# EG4S20BG256_CoreBoard_A0_NATIVE.net
KiCad netlist of a schematic drawn in Altium Designer
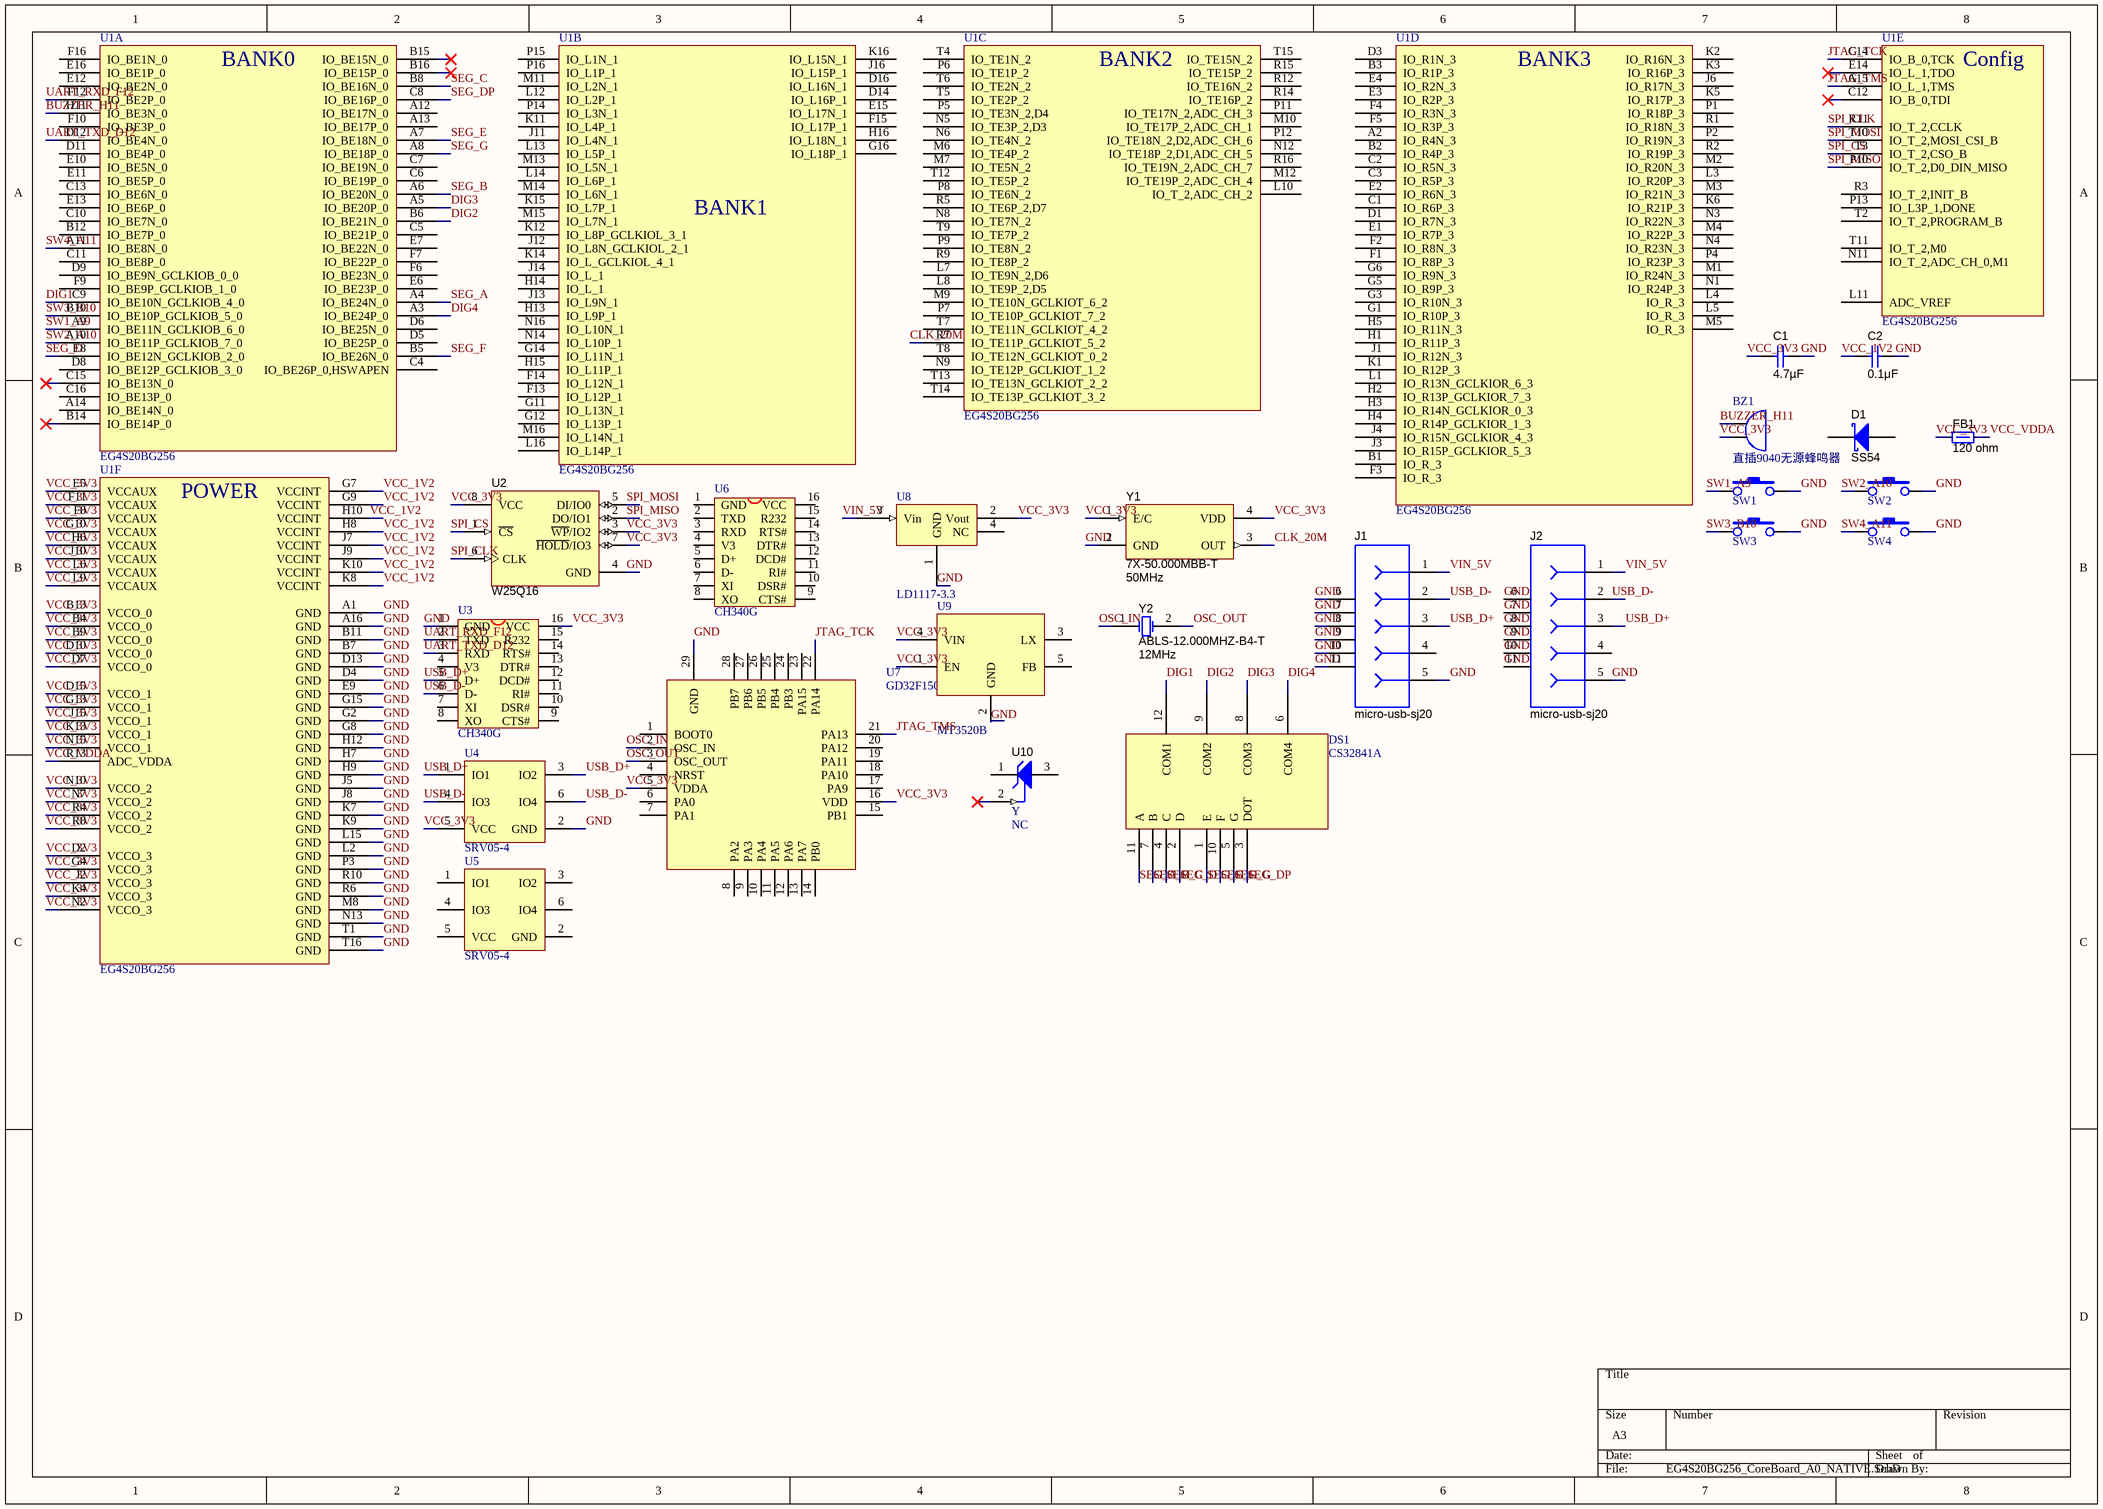
[diagram p0: EG4S20BG256_CoreBoard_A0_NATIVE.SchDoc]

(export (version "E")
  (design (tool "Eeschema 10.0.6"))
  (components
    (comp (ref "BZ1")
      (value "直插9040无源蜂鸣器")
      (footprint "BUZZER_9*9_4MM")
      (description "Buzzer, 74 dB min, 25V p-p, 8500pF @ 1kHz，直插9040无源蜂鸣器")
      (fields (field (name "MANUFACTURER") "Panasonic"))
      (libsource (lib "ANLOGIC开发板封装库") (part "BUZZER_EFBAA14D001"))
    )
    (comp (ref "C1")
      (value "GRM21BC81C475KA88L")
      (footprint "0805_HV")
      (description "CAP, CERM, 4.7 µF, 16 V, +/- 10%, X6S, 0805")
      (fields
        (field (name "VALUEDISPLAYED") "4.7µF")
        (field (name "MANUFACTURER") "MuRata")
        (field (name "PUBLISHER") "Texas Instruments")
      )
      (libsource (lib "ANLOGIC开发板封装库") (part "GRM21BC81C475KA88L"))
    )
    (comp (ref "C2")
      (value "C1005X7R1H104M")
      (footprint "0402")
      (description "CAP, CERM, 0.1 μF, 50 V, +/- 20%, X7R, 0402")
      (fields
        (field (name "VALUEDISPLAYED") "0.1μF")
        (field (name "MANUFACTURER") "TDK")
        (field (name "PUBLISHER") "Texas Instruments")
      )
      (libsource (lib "ANLOGIC开发板封装库") (part "C1005X7R1H104M_1"))
    )
    (comp (ref "D1")
      (value "SS54")
      (footprint "SMB")
      (description "Diode, Schottky, 40 V, 3A, SMB")
      (fields (field (name "MANUFACTURER") "Diodes Inc.") (field (name "PUBLISHER") "Texas Instruments"))
      (libsource (lib "ANLOGIC开发板封装库") (part "B340B-13-F"))
    )
    (comp (ref "DS1")
      (value "CS32841A")
      (footprint "CS2845AUR")
      (description "4位共阴数码管，红色")
      (libsource (lib "ANLOGIC开发板封装库") (part "4LED-ANODE"))
    )
    (comp (ref "FB1")
      (value "120 ohm")
      (footprint "0805_HV")
      (description "Ferrite Bead, 120 ohm @ 100 MHz, 0.2 A, 0805")
      (fields
        (field (name "PARTNUMBER") "GZ2012V121TF")
        (field (name "MANUFACTURER") "MuRata")
        (field (name "PUBLISHER") "Texas Instruments")
      )
      (libsource (lib "ANLOGIC开发板封装库") (part "BLM21BD121SN1D"))
    )
    (comp (ref "J1")
      (value "micro-usb-sj20")
      (footprint "YQMICRO-USB-SJ20")
      (description "Receptacle, Micro-USB-B, Right Angle, SMD")
      (fields
        (field (name "MANUFACTURER") "Molex")
        (field (name "SYMBOLCREATOR") "a0412235")
        (field (name "PUBLISHER") "Texas Instruments")
      )
      (libsource (lib "ANLOGIC开发板封装库") (part "105017-0001"))
    )
    (comp (ref "J2")
      (value "micro-usb-sj20")
      (footprint "YQMICRO-USB-SJ20")
      (description "Receptacle, Micro-USB-B, Right Angle, SMD")
      (fields
        (field (name "MANUFACTURER") "Molex")
        (field (name "SYMBOLCREATOR") "a0412235")
        (field (name "PUBLISHER") "Texas Instruments")
      )
      (libsource (lib "ANLOGIC开发板封装库") (part "105017-0001"))
    )
    (comp (ref "SW1")
      (value "贴片按键")
      (footprint "BUTTOM_T_6*6 *4.3")
      (description "米黄色圆形按键6*6*3.4")
      (libsource (lib "ANLOGIC开发板封装库") (part "SW-PB"))
    )
    (comp (ref "SW2")
      (value "贴片按键")
      (footprint "BUTTOM_T_6*6 *4.3")
      (description "米黄色圆形按键6*6*3.4")
      (libsource (lib "ANLOGIC开发板封装库") (part "SW-PB"))
    )
    (comp (ref "SW3")
      (value "贴片按键")
      (footprint "BUTTOM_T_6*6 *4.3")
      (description "米黄色圆形按键6*6*3.4")
      (libsource (lib "ANLOGIC开发板封装库") (part "SW-PB"))
    )
    (comp (ref "SW4")
      (value "贴片按键")
      (footprint "BUTTOM_T_6*6 *4.3")
      (description "米黄色圆形按键6*6*3.4")
      (libsource (lib "ANLOGIC开发板封装库") (part "SW-PB"))
    )
    (comp (ref "U1")
      (value "EG4S20BG256")
      (footprint "FBGA256")
      (libsource (lib "ANLOGIC开发板封装库") (part "EG4S20BG256"))
    )
    (comp (ref "U2")
      (value "W25Q16")
      (footprint "MICT-MW-8_N")
      (description "2.5V 8M-Bit Serial Flash Memory with Dual and Quad SPI, SOIC-8")
      (fields
        (field (name "PARTNUMBER") "W25Q16")
        (field (name "MANUFACTURER") "Winbond")
        (field (name "SYMBOLCREATOR") "Altium")
        (field (name "PUBLISHER") "Texas Instruments")
      )
      (libsource (lib "ANLOGIC开发板封装库") (part "W25Q80BLSNIG"))
    )
    (comp (ref "U3")
      (value "CH340G")
      (footprint "SOP16M")
      (description "USB2UART")
      (libsource (lib "ANLOGIC开发板封装库") (part "CH340G"))
    )
    (comp (ref "U4")
      (value "SRV05-4")
      (footprint "DBV0006A_N")
      (fields
        (field (name "MANUFACTURER") "Texas Instruments")
        (field (name "PARTNUMBER") "TPD4E001DBVR")
        (field (name "ALTERNATE PARTNUMBER") "Equivalent")
      )
      (libsource (lib "ANLOGIC开发板封装库") (part "TPD4E001DBVR"))
    )
    (comp (ref "U5")
      (value "SRV05-4")
      (footprint "DBV0006A_N")
      (fields
        (field (name "MANUFACTURER") "Texas Instruments")
        (field (name "PARTNUMBER") "TPD4E001DBVR")
        (field (name "ALTERNATE PARTNUMBER") "Equivalent")
      )
      (libsource (lib "ANLOGIC开发板封装库") (part "TPD4E001DBVR"))
    )
    (comp (ref "U6")
      (value "CH340G")
      (footprint "SOP16M")
      (description "USB2UART")
      (libsource (lib "ANLOGIC开发板封装库") (part "CH340G"))
    )
    (comp (ref "U7")
      (value "GD32F150G8U6")
      (footprint "WQFN-28_L4.0-W4.0-P0.40-BL-EP")
      (description "GD32F150U")
      (libsource (lib "ANLOGIC开发板封装库") (part "GD32F150U"))
    )
    (comp (ref "U8")
      (value "LD1117-3.3")
      (footprint "SOT223-L")
      (description "LDO电源")
      (libsource (lib "ANLOGIC开发板封装库") (part "AMS1117"))
    )
    (comp (ref "U9")
      (value "MT3520B")
      (footprint "DBV0005A_N")
      (description "1MHZ,2A,STEP-DOWM DC/DC")
      (libsource (lib "ANLOGIC开发板封装库") (part "RT8097"))
    )
    (comp (ref "U10")
      (value "Y")
      (footprint "DBZ0003A_N")
      (description "PRECISION PROGRAMMABLE REFERENCE, DBZ0003A")
      (fields
        (field (name "PARTNUMBER") "TL431AIDBZ")
        (field (name "MANUFACTURER") "Texas Instruments")
        (field (name "IGNORE") "Y")
        (field (name "PARAMETER 1") "NC")
        (field (name "SYMBOLCREATOR") "a0412235")
        (field (name "PUBLISHER") "Texas Instruments")
      )
      (libsource (lib "ANLOGIC开发板封装库") (part "TL431AIDBZ"))
    )
    (comp (ref "Y1")
      (value "7X-50.000MBB-T")
      (footprint "XTAL_NX3225SA")
      (description "Crystal, 有源晶振，Sealed Locked 50MHz, 15pF, SMD")
      (fields
        (field (name "MANUFACTURER") "TXC Corporation")
        (field (name "FREQUENCY") "50MHz")
        (field (name "SYMBOLCREATOR") "a0799628")
        (field (name "PUBLISHER") "Texas Instruments")
      )
      (libsource (lib "ANLOGIC开发板封装库") (part "7X-20.000MBB-T_1"))
    )
    (comp (ref "Y2")
      (value "ABLS-12.000MHZ-B4-T")
      (footprint "YQ_OSC5032")
      (description "Crystal, 12MHz, 18pF, SMD,无源")
      (fields
        (field (name "FREQUENCY") "12MHz")
        (field (name "MANUFACTURER") "Abracon Corportation")
        (field (name "SYMBOLCREATOR") "a0412235")
        (field (name "PUBLISHER") "Texas Instruments")
      )
      (libsource (lib "ANLOGIC开发板封装库") (part "ABLS-8.000MHZ-B4-T"))
    )
  )
  (nets
    (net (code "1") (name "/BUZZER_H11") (class "Default")
      (node (ref "BZ1") (pin "1") (pintype "passive"))
      (node (ref "U1") (pin "H11") (pinfunction "IO_BE3N_0_H11") (pintype "passive"))
    )
    (net (code "2") (name "/CLK_20M") (class "Default")
      (node (ref "U1") (pin "R7") (pinfunction "IO_TE11P_GCLKIOT_5_2_R7") (pintype "passive"))
      (node (ref "Y1") (pin "3") (pinfunction "OUT_3") (pintype "output"))
    )
    (net (code "3") (name "/DIG1") (class "Default")
      (node (ref "DS1") (pin "12") (pinfunction "COM1_12") (pintype "passive"))
      (node (ref "U1") (pin "C9") (pinfunction "IO_BE10N_GCLKIOB_4_0_C9") (pintype "passive"))
    )
    (net (code "4") (name "/DIG2") (class "Default")
      (node (ref "DS1") (pin "9") (pinfunction "COM2_9") (pintype "passive"))
      (node (ref "U1") (pin "B6") (pinfunction "IO_BE21N_0_B6") (pintype "passive"))
    )
    (net (code "5") (name "/DIG3") (class "Default")
      (node (ref "DS1") (pin "8") (pinfunction "COM3_8") (pintype "passive"))
      (node (ref "U1") (pin "A5") (pinfunction "IO_BE20P_0_A5") (pintype "passive"))
    )
    (net (code "6") (name "/DIG4") (class "Default")
      (node (ref "DS1") (pin "6") (pinfunction "COM4_6") (pintype "passive"))
      (node (ref "U1") (pin "A3") (pinfunction "IO_BE24P_0_A3") (pintype "passive"))
    )
    (net (code "7") (name "/GND") (class "Default")
      (node (ref "C1") (pin "1") (pinfunction "1_1") (pintype "passive"))
      (node (ref "C2") (pin "1") (pinfunction "1_1") (pintype "passive"))
      (node (ref "J1") (pin "10") (pintype "passive"))
      (node (ref "J1") (pin "11") (pintype "passive"))
      (node (ref "J1") (pin "5") (pintype "passive"))
      (node (ref "J1") (pin "6") (pintype "passive"))
      (node (ref "J1") (pin "7") (pintype "passive"))
      (node (ref "J1") (pin "8") (pintype "passive"))
      (node (ref "J1") (pin "9") (pintype "passive"))
      (node (ref "J2") (pin "10") (pintype "passive"))
      (node (ref "J2") (pin "11") (pintype "passive"))
      (node (ref "J2") (pin "5") (pintype "passive"))
      (node (ref "J2") (pin "6") (pintype "passive"))
      (node (ref "J2") (pin "7") (pintype "passive"))
      (node (ref "J2") (pin "8") (pintype "passive"))
      (node (ref "J2") (pin "9") (pintype "passive"))
      (node (ref "SW1") (pin "2") (pintype "passive"))
      (node (ref "SW2") (pin "2") (pintype "passive"))
      (node (ref "SW3") (pin "2") (pintype "passive"))
      (node (ref "SW4") (pin "2") (pintype "passive"))
      (node (ref "U1") (pin "A1") (pinfunction "GND_A1") (pintype "passive"))
      (node (ref "U1") (pin "A16") (pinfunction "GND_A16") (pintype "passive"))
      (node (ref "U1") (pin "B11") (pinfunction "GND_B11") (pintype "passive"))
      (node (ref "U1") (pin "B7") (pinfunction "GND_B7") (pintype "passive"))
      (node (ref "U1") (pin "D13") (pinfunction "GND_D13") (pintype "passive"))
      (node (ref "U1") (pin "D4") (pinfunction "GND_D4") (pintype "passive"))
      (node (ref "U1") (pin "E9") (pinfunction "GND_E9") (pintype "passive"))
      (node (ref "U1") (pin "G15") (pinfunction "GND_G15") (pintype "passive"))
      (node (ref "U1") (pin "G2") (pinfunction "GND_G2") (pintype "passive"))
      (node (ref "U1") (pin "G8") (pinfunction "GND_G8") (pintype "passive"))
      (node (ref "U1") (pin "H12") (pinfunction "GND_H12") (pintype "passive"))
      (node (ref "U1") (pin "H7") (pinfunction "GND_H7") (pintype "passive"))
      (node (ref "U1") (pin "H9") (pinfunction "GND_H9") (pintype "passive"))
      (node (ref "U1") (pin "J5") (pinfunction "GND_J5") (pintype "passive"))
      (node (ref "U1") (pin "J8") (pinfunction "GND_J8") (pintype "passive"))
      (node (ref "U1") (pin "K7") (pinfunction "GND_K7") (pintype "passive"))
      (node (ref "U1") (pin "K9") (pinfunction "GND_K9") (pintype "passive"))
      (node (ref "U1") (pin "L15") (pinfunction "GND_L15") (pintype "passive"))
      (node (ref "U1") (pin "L2") (pinfunction "GND_L2") (pintype "passive"))
      (node (ref "U1") (pin "M8") (pinfunction "GND_M8") (pintype "passive"))
      (node (ref "U1") (pin "N13") (pinfunction "GND_N13") (pintype "passive"))
      (node (ref "U1") (pin "P3") (pinfunction "GND_P3") (pintype "passive"))
      (node (ref "U1") (pin "R10") (pinfunction "GND_R10") (pintype "passive"))
      (node (ref "U1") (pin "R6") (pinfunction "GND_R6") (pintype "passive"))
      (node (ref "U1") (pin "T1") (pinfunction "GND_T1") (pintype "passive"))
      (node (ref "U1") (pin "T16") (pinfunction "GND_T16") (pintype "passive"))
      (node (ref "U2") (pin "4") (pinfunction "GND_4") (pintype "power_in"))
      (node (ref "U3") (pin "1") (pinfunction "GND_1") (pintype "passive"))
      (node (ref "U4") (pin "2") (pinfunction "GND_2") (pintype "power_in"))
      (node (ref "U7") (pin "29") (pinfunction "GND_29") (pintype "passive"))
      (node (ref "U8") (pin "1") (pinfunction "GND_1") (pintype "power_in"))
      (node (ref "U9") (pin "2") (pinfunction "GND_2") (pintype "passive"))
      (node (ref "Y1") (pin "2") (pinfunction "GND_2") (pintype "power_in"))
    )
    (net (code "8") (name "/JTAG_TCK") (class "Default")
      (node (ref "U1") (pin "C14") (pinfunction "IO_B_0,TCK_C14") (pintype "passive"))
      (node (ref "U7") (pin "22") (pinfunction "PA14_22") (pintype "passive"))
    )
    (net (code "9") (name "/JTAG_TMS") (class "Default")
      (node (ref "U1") (pin "A15") (pinfunction "IO_L_1,TMS_A15") (pintype "passive"))
      (node (ref "U7") (pin "21") (pinfunction "PA13_21") (pintype "passive"))
    )
    (net (code "10") (name "/OSC_IN") (class "Default")
      (node (ref "U7") (pin "2") (pinfunction "OSC_IN_2") (pintype "passive"))
      (node (ref "Y2") (pin "1") (pinfunction "OSC1_1") (pintype "passive"))
    )
    (net (code "11") (name "/OSC_OUT") (class "Default")
      (node (ref "U7") (pin "3") (pinfunction "OSC_OUT_3") (pintype "passive"))
      (node (ref "Y2") (pin "2") (pinfunction "OSC2_2") (pintype "passive"))
    )
    (net (code "12") (name "/SEG_A") (class "Default")
      (node (ref "DS1") (pin "11") (pinfunction "A_11") (pintype "passive"))
      (node (ref "U1") (pin "A4") (pinfunction "IO_BE24N_0_A4") (pintype "passive"))
    )
    (net (code "13") (name "/SEG_B") (class "Default")
      (node (ref "DS1") (pin "7") (pinfunction "B_7") (pintype "passive"))
      (node (ref "U1") (pin "A6") (pinfunction "IO_BE20N_0_A6") (pintype "passive"))
    )
    (net (code "14") (name "/SEG_C") (class "Default")
      (node (ref "DS1") (pin "4") (pinfunction "C_4") (pintype "passive"))
      (node (ref "U1") (pin "B8") (pinfunction "IO_BE16N_0_B8") (pintype "passive"))
    )
    (net (code "15") (name "/SEG_D") (class "Default")
      (node (ref "DS1") (pin "2") (pinfunction "D_2") (pintype "passive"))
      (node (ref "U1") (pin "E8") (pinfunction "IO_BE12N_GCLKIOB_2_0_E8") (pintype "passive"))
    )
    (net (code "16") (name "/SEG_DP") (class "Default")
      (node (ref "DS1") (pin "3") (pinfunction "DOT_3") (pintype "passive"))
      (node (ref "U1") (pin "C8") (pinfunction "IO_BE16P_0_C8") (pintype "passive"))
    )
    (net (code "17") (name "/SEG_E") (class "Default")
      (node (ref "DS1") (pin "1") (pinfunction "E_1") (pintype "passive"))
      (node (ref "U1") (pin "A7") (pinfunction "IO_BE18N_0_A7") (pintype "passive"))
    )
    (net (code "18") (name "/SEG_F") (class "Default")
      (node (ref "DS1") (pin "10") (pinfunction "F_10") (pintype "passive"))
      (node (ref "U1") (pin "B5") (pinfunction "IO_BE26N_0_B5") (pintype "passive"))
    )
    (net (code "19") (name "/SEG_G") (class "Default")
      (node (ref "DS1") (pin "5") (pinfunction "G_5") (pintype "passive"))
      (node (ref "U1") (pin "A8") (pinfunction "IO_BE18P_0_A8") (pintype "passive"))
    )
    (net (code "20") (name "/SPI_CLK") (class "Default")
      (node (ref "U1") (pin "R11") (pinfunction "IO_T_2,CCLK_R11") (pintype "passive"))
      (node (ref "U2") (pin "6") (pinfunction "CLK_6") (pintype "input"))
    )
    (net (code "21") (name "/SPI_CS") (class "Default")
      (node (ref "U1") (pin "T3") (pinfunction "IO_T_2,CSO_B_T3") (pintype "passive"))
      (node (ref "U2") (pin "1") (pinfunction "~{CS}_1") (pintype "input"))
    )
    (net (code "22") (name "/SPI_MISO") (class "Default")
      (node (ref "U1") (pin "P10") (pinfunction "IO_T_2,D0_DIN_MISO_P10") (pintype "passive"))
      (node (ref "U2") (pin "2") (pinfunction "DO/IO1_2") (pintype "bidirectional"))
    )
    (net (code "23") (name "/SPI_MOSI") (class "Default")
      (node (ref "U1") (pin "T10") (pinfunction "IO_T_2,MOSI_CSI_B_T10") (pintype "passive"))
      (node (ref "U2") (pin "5") (pinfunction "DI/IO0_5") (pintype "bidirectional"))
    )
    (net (code "24") (name "/SW1_A9") (class "Default")
      (node (ref "SW1") (pin "1") (pintype "passive"))
      (node (ref "U1") (pin "A9") (pinfunction "IO_BE11N_GCLKIOB_6_0_A9") (pintype "passive"))
    )
    (net (code "25") (name "/SW2_A10") (class "Default")
      (node (ref "SW2") (pin "1") (pintype "passive"))
      (node (ref "U1") (pin "A10") (pinfunction "IO_BE11P_GCLKIOB_7_0_A10") (pintype "passive"))
    )
    (net (code "26") (name "/SW3_B10") (class "Default")
      (node (ref "SW3") (pin "1") (pintype "passive"))
      (node (ref "U1") (pin "B10") (pinfunction "IO_BE10P_GCLKIOB_5_0_B10") (pintype "passive"))
    )
    (net (code "27") (name "/SW4_A11") (class "Default")
      (node (ref "SW4") (pin "1") (pintype "passive"))
      (node (ref "U1") (pin "A11") (pinfunction "IO_BE8N_0_A11") (pintype "passive"))
    )
    (net (code "28") (name "/UART_RXD_F12") (class "Default")
      (node (ref "U1") (pin "F12") (pinfunction "IO_BE2P_0_F12") (pintype "passive"))
      (node (ref "U3") (pin "2") (pinfunction "TXD_2") (pintype "passive"))
    )
    (net (code "29") (name "/UART_TXD_D12") (class "Default")
      (node (ref "U1") (pin "D12") (pinfunction "IO_BE4N_0_D12") (pintype "passive"))
      (node (ref "U3") (pin "3") (pinfunction "RXD_3") (pintype "passive"))
    )
    (net (code "30") (name "/USB_D+") (class "Default")
      (node (ref "J1") (pin "3") (pintype "passive"))
      (node (ref "J2") (pin "3") (pintype "passive"))
      (node (ref "U3") (pin "5") (pinfunction "D+_5") (pintype "passive"))
      (node (ref "U4") (pin "1") (pinfunction "IO1_1") (pintype "passive"))
      (node (ref "U4") (pin "3") (pinfunction "IO2_3") (pintype "passive"))
    )
    (net (code "31") (name "/USB_D-") (class "Default")
      (node (ref "J1") (pin "2") (pintype "passive"))
      (node (ref "J2") (pin "2") (pintype "passive"))
      (node (ref "U3") (pin "6") (pinfunction "D-_6") (pintype "passive"))
      (node (ref "U4") (pin "4") (pinfunction "IO3_4") (pintype "passive"))
      (node (ref "U4") (pin "6") (pinfunction "IO4_6") (pintype "passive"))
    )
    (net (code "32") (name "/VCC_1V2") (class "Default")
      (node (ref "C2") (pin "2") (pinfunction "2_2") (pintype "passive"))
      (node (ref "U1") (pin "G7") (pinfunction "VCCINT_G7") (pintype "passive"))
      (node (ref "U1") (pin "G9") (pinfunction "VCCINT_G9") (pintype "passive"))
      (node (ref "U1") (pin "H10") (pinfunction "VCCINT_H10") (pintype "passive"))
      (node (ref "U1") (pin "H8") (pinfunction "VCCINT_H8") (pintype "passive"))
      (node (ref "U1") (pin "J7") (pinfunction "VCCINT_J7") (pintype "passive"))
      (node (ref "U1") (pin "J9") (pinfunction "VCCINT_J9") (pintype "passive"))
      (node (ref "U1") (pin "K10") (pinfunction "VCCINT_K10") (pintype "passive"))
      (node (ref "U1") (pin "K8") (pinfunction "VCCINT_K8") (pintype "passive"))
    )
    (net (code "33") (name "/VCC_3V3") (class "Default")
      (node (ref "BZ1") (pin "2") (pintype "passive"))
      (node (ref "C1") (pin "2") (pinfunction "2_2") (pintype "passive"))
      (node (ref "FB1") (pin "1") (pinfunction "1_1") (pintype "passive"))
      (node (ref "U1") (pin "B13") (pinfunction "VCCO_0_B13") (pintype "passive"))
      (node (ref "U1") (pin "B4") (pinfunction "VCCO_0_B4") (pintype "passive"))
      (node (ref "U1") (pin "B9") (pinfunction "VCCO_0_B9") (pintype "passive"))
      (node (ref "U1") (pin "D10") (pinfunction "VCCO_0_D10") (pintype "passive"))
      (node (ref "U1") (pin "D15") (pinfunction "VCCO_1_D15") (pintype "passive"))
      (node (ref "U1") (pin "D2") (pinfunction "VCCO_3_D2") (pintype "passive"))
      (node (ref "U1") (pin "D7") (pinfunction "VCCO_0_D7") (pintype "passive"))
      (node (ref "U1") (pin "E5") (pinfunction "VCCAUX_E5") (pintype "passive"))
      (node (ref "U1") (pin "F11") (pinfunction "VCCAUX_F11") (pintype "passive"))
      (node (ref "U1") (pin "F8") (pinfunction "VCCAUX_F8") (pintype "passive"))
      (node (ref "U1") (pin "G10") (pinfunction "VCCAUX_G10") (pintype "passive"))
      (node (ref "U1") (pin "G13") (pinfunction "VCCO_1_G13") (pintype "passive"))
      (node (ref "U1") (pin "G4") (pinfunction "VCCO_3_G4") (pintype "passive"))
      (node (ref "U1") (pin "H6") (pinfunction "VCCAUX_H6") (pintype "passive"))
      (node (ref "U1") (pin "J10") (pinfunction "VCCAUX_J10") (pintype "passive"))
      (node (ref "U1") (pin "J15") (pinfunction "VCCO_1_J15") (pintype "passive"))
      (node (ref "U1") (pin "J2") (pinfunction "VCCO_3_J2") (pintype "passive"))
      (node (ref "U1") (pin "K13") (pinfunction "VCCO_1_K13") (pintype "passive"))
      (node (ref "U1") (pin "K4") (pinfunction "VCCO_3_K4") (pintype "passive"))
      (node (ref "U1") (pin "L6") (pinfunction "VCCAUX_L6") (pintype "passive"))
      (node (ref "U1") (pin "L9") (pinfunction "VCCAUX_L9") (pintype "passive"))
      (node (ref "U1") (pin "N10") (pinfunction "VCCO_2_N10") (pintype "passive"))
      (node (ref "U1") (pin "N15") (pinfunction "VCCO_1_N15") (pintype "passive"))
      (node (ref "U1") (pin "N2") (pinfunction "VCCO_3_N2") (pintype "passive"))
      (node (ref "U1") (pin "N7") (pinfunction "VCCO_2_N7") (pintype "passive"))
      (node (ref "U1") (pin "R4") (pinfunction "VCCO_2_R4") (pintype "passive"))
      (node (ref "U1") (pin "R8") (pinfunction "VCCO_2_R8") (pintype "passive"))
      (node (ref "U2") (pin "3") (pinfunction "~{WP}/IO2_3") (pintype "bidirectional"))
      (node (ref "U2") (pin "7") (pinfunction "~{HOLD}/IO3_7") (pintype "bidirectional"))
      (node (ref "U2") (pin "8") (pinfunction "VCC_8") (pintype "power_in"))
      (node (ref "U3") (pin "16") (pinfunction "VCC_16") (pintype "passive"))
      (node (ref "U4") (pin "5") (pinfunction "VCC_5") (pintype "power_in"))
      (node (ref "U7") (pin "16") (pinfunction "VDD_16") (pintype "passive"))
      (node (ref "U7") (pin "5") (pinfunction "VDDA_5") (pintype "passive"))
      (node (ref "U8") (pin "2") (pinfunction "Vout_2") (pintype "power_in"))
      (node (ref "U9") (pin "1") (pinfunction "EN_1") (pintype "passive"))
      (node (ref "U9") (pin "4") (pinfunction "VIN_4") (pintype "passive"))
      (node (ref "Y1") (pin "1") (pinfunction "E/C_1") (pintype "input"))
      (node (ref "Y1") (pin "4") (pinfunction "VDD_4") (pintype "power_in"))
    )
    (net (code "34") (name "/VCC_VDDA") (class "Default")
      (node (ref "FB1") (pin "2") (pinfunction "2_2") (pintype "passive"))
      (node (ref "U1") (pin "R13") (pinfunction "ADC_VDDA_R13") (pintype "passive"))
    )
    (net (code "35") (name "/VIN_5V") (class "Default")
      (node (ref "J1") (pin "1") (pintype "passive"))
      (node (ref "J2") (pin "1") (pintype "passive"))
      (node (ref "U8") (pin "3") (pinfunction "Vin_3") (pintype "input"))
    )
    (net (code "36") (name "unconnected-(D1-A-Pad2)") (class "Default")
      (node (ref "D1") (pin "2") (pinfunction "A_2") (pintype "passive"))
    )
    (net (code "37") (name "unconnected-(D1-K-Pad1)") (class "Default")
      (node (ref "D1") (pin "1") (pinfunction "K_1") (pintype "passive"))
    )
    (net (code "38") (name "unconnected-(J1-Pad4)") (class "Default")
      (node (ref "J1") (pin "4") (pintype "passive"))
    )
    (net (code "39") (name "unconnected-(J2-Pad4)") (class "Default")
      (node (ref "J2") (pin "4") (pintype "passive"))
    )
    (net (code "40") (name "unconnected-(U1A-IO_BE1N_0-PadF16)") (class "Default")
      (node (ref "U1") (pin "F16") (pinfunction "IO_BE1N_0_F16") (pintype "passive"))
    )
    (net (code "41") (name "unconnected-(U1A-IO_BE1P_0-PadE16)") (class "Default")
      (node (ref "U1") (pin "E16") (pinfunction "IO_BE1P_0_E16") (pintype "passive"))
    )
    (net (code "42") (name "unconnected-(U1A-IO_BE2N_0-PadE12)") (class "Default")
      (node (ref "U1") (pin "E12") (pinfunction "IO_BE2N_0_E12") (pintype "passive"))
    )
    (net (code "43") (name "unconnected-(U1A-IO_BE3P_0-PadF10)") (class "Default")
      (node (ref "U1") (pin "F10") (pinfunction "IO_BE3P_0_F10") (pintype "passive"))
    )
    (net (code "44") (name "unconnected-(U1A-IO_BE4P_0-PadD11)") (class "Default")
      (node (ref "U1") (pin "D11") (pinfunction "IO_BE4P_0_D11") (pintype "passive"))
    )
    (net (code "45") (name "unconnected-(U1A-IO_BE5N_0-PadE10)") (class "Default")
      (node (ref "U1") (pin "E10") (pinfunction "IO_BE5N_0_E10") (pintype "passive"))
    )
    (net (code "46") (name "unconnected-(U1A-IO_BE5P_0-PadE11)") (class "Default")
      (node (ref "U1") (pin "E11") (pinfunction "IO_BE5P_0_E11") (pintype "passive"))
    )
    (net (code "47") (name "unconnected-(U1A-IO_BE6N_0-PadC13)") (class "Default")
      (node (ref "U1") (pin "C13") (pinfunction "IO_BE6N_0_C13") (pintype "passive"))
    )
    (net (code "48") (name "unconnected-(U1A-IO_BE6P_0-PadE13)") (class "Default")
      (node (ref "U1") (pin "E13") (pinfunction "IO_BE6P_0_E13") (pintype "passive"))
    )
    (net (code "49") (name "unconnected-(U1A-IO_BE7N_0-PadC10)") (class "Default")
      (node (ref "U1") (pin "C10") (pinfunction "IO_BE7N_0_C10") (pintype "passive"))
    )
    (net (code "50") (name "unconnected-(U1A-IO_BE7P_0-PadB12)") (class "Default")
      (node (ref "U1") (pin "B12") (pinfunction "IO_BE7P_0_B12") (pintype "passive"))
    )
    (net (code "51") (name "unconnected-(U1A-IO_BE8P_0-PadC11)") (class "Default")
      (node (ref "U1") (pin "C11") (pinfunction "IO_BE8P_0_C11") (pintype "passive"))
    )
    (net (code "52") (name "unconnected-(U1A-IO_BE9N_GCLKIOB_0_0-PadD9)") (class "Default")
      (node (ref "U1") (pin "D9") (pinfunction "IO_BE9N_GCLKIOB_0_0_D9") (pintype "passive"))
    )
    (net (code "53") (name "unconnected-(U1A-IO_BE9P_GCLKIOB_1_0-PadF9)") (class "Default")
      (node (ref "U1") (pin "F9") (pinfunction "IO_BE9P_GCLKIOB_1_0_F9") (pintype "passive"))
    )
    (net (code "54") (name "unconnected-(U1A-IO_BE12P_GCLKIOB_3_0-PadD8)") (class "Default")
      (node (ref "U1") (pin "D8") (pinfunction "IO_BE12P_GCLKIOB_3_0_D8") (pintype "passive"))
    )
    (net (code "55") (name "unconnected-(U1A-IO_BE13N_0-PadC15)") (class "Default")
      (node (ref "U1") (pin "C15") (pinfunction "IO_BE13N_0_C15") (pintype "passive+no_connect"))
    )
    (net (code "56") (name "unconnected-(U1A-IO_BE13P_0-PadC16)") (class "Default")
      (node (ref "U1") (pin "C16") (pinfunction "IO_BE13P_0_C16") (pintype "passive"))
    )
    (net (code "57") (name "unconnected-(U1A-IO_BE14N_0-PadA14)") (class "Default")
      (node (ref "U1") (pin "A14") (pinfunction "IO_BE14N_0_A14") (pintype "passive"))
    )
    (net (code "58") (name "unconnected-(U1A-IO_BE14P_0-PadB14)") (class "Default")
      (node (ref "U1") (pin "B14") (pinfunction "IO_BE14P_0_B14") (pintype "passive+no_connect"))
    )
    (net (code "59") (name "unconnected-(U1A-IO_BE15N_0-PadB15)") (class "Default")
      (node (ref "U1") (pin "B15") (pinfunction "IO_BE15N_0_B15") (pintype "passive+no_connect"))
    )
    (net (code "60") (name "unconnected-(U1A-IO_BE15P_0-PadB16)") (class "Default")
      (node (ref "U1") (pin "B16") (pinfunction "IO_BE15P_0_B16") (pintype "passive+no_connect"))
    )
    (net (code "61") (name "unconnected-(U1A-IO_BE17N_0-PadA12)") (class "Default")
      (node (ref "U1") (pin "A12") (pinfunction "IO_BE17N_0_A12") (pintype "passive"))
    )
    (net (code "62") (name "unconnected-(U1A-IO_BE17P_0-PadA13)") (class "Default")
      (node (ref "U1") (pin "A13") (pinfunction "IO_BE17P_0_A13") (pintype "passive"))
    )
    (net (code "63") (name "unconnected-(U1A-IO_BE19N_0-PadC7)") (class "Default")
      (node (ref "U1") (pin "C7") (pinfunction "IO_BE19N_0_C7") (pintype "passive"))
    )
    (net (code "64") (name "unconnected-(U1A-IO_BE19P_0-PadC6)") (class "Default")
      (node (ref "U1") (pin "C6") (pinfunction "IO_BE19P_0_C6") (pintype "passive"))
    )
    (net (code "65") (name "unconnected-(U1A-IO_BE21P_0-PadC5)") (class "Default")
      (node (ref "U1") (pin "C5") (pinfunction "IO_BE21P_0_C5") (pintype "passive"))
    )
    (net (code "66") (name "unconnected-(U1A-IO_BE22N_0-PadE7)") (class "Default")
      (node (ref "U1") (pin "E7") (pinfunction "IO_BE22N_0_E7") (pintype "passive"))
    )
    (net (code "67") (name "unconnected-(U1A-IO_BE22P_0-PadF7)") (class "Default")
      (node (ref "U1") (pin "F7") (pinfunction "IO_BE22P_0_F7") (pintype "passive"))
    )
    (net (code "68") (name "unconnected-(U1A-IO_BE23N_0-PadF6)") (class "Default")
      (node (ref "U1") (pin "F6") (pinfunction "IO_BE23N_0_F6") (pintype "passive"))
    )
    (net (code "69") (name "unconnected-(U1A-IO_BE23P_0-PadE6)") (class "Default")
      (node (ref "U1") (pin "E6") (pinfunction "IO_BE23P_0_E6") (pintype "passive"))
    )
    (net (code "70") (name "unconnected-(U1A-IO_BE25N_0-PadD6)") (class "Default")
      (node (ref "U1") (pin "D6") (pinfunction "IO_BE25N_0_D6") (pintype "passive"))
    )
    (net (code "71") (name "unconnected-(U1A-IO_BE25P_0-PadD5)") (class "Default")
      (node (ref "U1") (pin "D5") (pinfunction "IO_BE25P_0_D5") (pintype "passive"))
    )
    (net (code "72") (name "unconnected-(U1A-IO_BE26P_0,HSWAPEN-PadC4)") (class "Default")
      (node (ref "U1") (pin "C4") (pinfunction "IO_BE26P_0,HSWAPEN_C4") (pintype "passive"))
    )
    (net (code "73") (name "unconnected-(U1B-IO_L1N_1-PadP15)") (class "Default")
      (node (ref "U1") (pin "P15") (pinfunction "IO_L1N_1_P15") (pintype "passive"))
    )
    (net (code "74") (name "unconnected-(U1B-IO_L1P_1-PadP16)") (class "Default")
      (node (ref "U1") (pin "P16") (pinfunction "IO_L1P_1_P16") (pintype "passive"))
    )
    (net (code "75") (name "unconnected-(U1B-IO_L2N_1-PadM11)") (class "Default")
      (node (ref "U1") (pin "M11") (pinfunction "IO_L2N_1_M11") (pintype "passive"))
    )
    (net (code "76") (name "unconnected-(U1B-IO_L2P_1-PadL12)") (class "Default")
      (node (ref "U1") (pin "L12") (pinfunction "IO_L2P_1_L12") (pintype "passive"))
    )
    (net (code "77") (name "unconnected-(U1B-IO_L3N_1-PadP14)") (class "Default")
      (node (ref "U1") (pin "P14") (pinfunction "IO_L3N_1_P14") (pintype "passive"))
    )
    (net (code "78") (name "unconnected-(U1B-IO_L4N_1-PadJ11)") (class "Default")
      (node (ref "U1") (pin "J11") (pinfunction "IO_L4N_1_J11") (pintype "passive"))
    )
    (net (code "79") (name "unconnected-(U1B-IO_L4P_1-PadK11)") (class "Default")
      (node (ref "U1") (pin "K11") (pinfunction "IO_L4P_1_K11") (pintype "passive"))
    )
    (net (code "80") (name "unconnected-(U1B-IO_L5N_1-PadM13)") (class "Default")
      (node (ref "U1") (pin "M13") (pinfunction "IO_L5N_1_M13") (pintype "passive"))
    )
    (net (code "81") (name "unconnected-(U1B-IO_L5P_1-PadL13)") (class "Default")
      (node (ref "U1") (pin "L13") (pinfunction "IO_L5P_1_L13") (pintype "passive"))
    )
    (net (code "82") (name "unconnected-(U1B-IO_L6N_1-PadM14)") (class "Default")
      (node (ref "U1") (pin "M14") (pinfunction "IO_L6N_1_M14") (pintype "passive"))
    )
    (net (code "83") (name "unconnected-(U1B-IO_L6P_1-PadL14)") (class "Default")
      (node (ref "U1") (pin "L14") (pinfunction "IO_L6P_1_L14") (pintype "passive"))
    )
    (net (code "84") (name "unconnected-(U1B-IO_L7N_1-PadM15)") (class "Default")
      (node (ref "U1") (pin "M15") (pinfunction "IO_L7N_1_M15") (pintype "passive"))
    )
    (net (code "85") (name "unconnected-(U1B-IO_L7P_1-PadK15)") (class "Default")
      (node (ref "U1") (pin "K15") (pinfunction "IO_L7P_1_K15") (pintype "passive"))
    )
    (net (code "86") (name "unconnected-(U1B-IO_L8N_GCLKIOL_2_1-PadJ12)") (class "Default")
      (node (ref "U1") (pin "J12") (pinfunction "IO_L8N_GCLKIOL_2_1_J12") (pintype "passive"))
    )
    (net (code "87") (name "unconnected-(U1B-IO_L8P_GCLKIOL_3_1-PadK12)") (class "Default")
      (node (ref "U1") (pin "K12") (pinfunction "IO_L8P_GCLKIOL_3_1_K12") (pintype "passive"))
    )
    (net (code "88") (name "unconnected-(U1B-IO_L9N_1-PadJ13)") (class "Default")
      (node (ref "U1") (pin "J13") (pinfunction "IO_L9N_1_J13") (pintype "passive"))
    )
    (net (code "89") (name "unconnected-(U1B-IO_L9P_1-PadH13)") (class "Default")
      (node (ref "U1") (pin "H13") (pinfunction "IO_L9P_1_H13") (pintype "passive"))
    )
    (net (code "90") (name "unconnected-(U1B-IO_L10N_1-PadN16)") (class "Default")
      (node (ref "U1") (pin "N16") (pinfunction "IO_L10N_1_N16") (pintype "passive"))
    )
    (net (code "91") (name "unconnected-(U1B-IO_L10P_1-PadN14)") (class "Default")
      (node (ref "U1") (pin "N14") (pinfunction "IO_L10P_1_N14") (pintype "passive"))
    )
    (net (code "92") (name "unconnected-(U1B-IO_L11N_1-PadG14)") (class "Default")
      (node (ref "U1") (pin "G14") (pinfunction "IO_L11N_1_G14") (pintype "passive"))
    )
    (net (code "93") (name "unconnected-(U1B-IO_L11P_1-PadH15)") (class "Default")
      (node (ref "U1") (pin "H15") (pinfunction "IO_L11P_1_H15") (pintype "passive"))
    )
    (net (code "94") (name "unconnected-(U1B-IO_L12N_1-PadF14)") (class "Default")
      (node (ref "U1") (pin "F14") (pinfunction "IO_L12N_1_F14") (pintype "passive"))
    )
    (net (code "95") (name "unconnected-(U1B-IO_L12P_1-PadF13)") (class "Default")
      (node (ref "U1") (pin "F13") (pinfunction "IO_L12P_1_F13") (pintype "passive"))
    )
    (net (code "96") (name "unconnected-(U1B-IO_L13N_1-PadG11)") (class "Default")
      (node (ref "U1") (pin "G11") (pinfunction "IO_L13N_1_G11") (pintype "passive"))
    )
    (net (code "97") (name "unconnected-(U1B-IO_L13P_1-PadG12)") (class "Default")
      (node (ref "U1") (pin "G12") (pinfunction "IO_L13P_1_G12") (pintype "passive"))
    )
    (net (code "98") (name "unconnected-(U1B-IO_L14N_1-PadM16)") (class "Default")
      (node (ref "U1") (pin "M16") (pinfunction "IO_L14N_1_M16") (pintype "passive"))
    )
    (net (code "99") (name "unconnected-(U1B-IO_L14P_1-PadL16)") (class "Default")
      (node (ref "U1") (pin "L16") (pinfunction "IO_L14P_1_L16") (pintype "passive"))
    )
    (net (code "100") (name "unconnected-(U1B-IO_L15N_1-PadK16)") (class "Default")
      (node (ref "U1") (pin "K16") (pinfunction "IO_L15N_1_K16") (pintype "passive"))
    )
    (net (code "101") (name "unconnected-(U1B-IO_L15P_1-PadJ16)") (class "Default")
      (node (ref "U1") (pin "J16") (pinfunction "IO_L15P_1_J16") (pintype "passive"))
    )
    (net (code "102") (name "unconnected-(U1B-IO_L16N_1-PadD16)") (class "Default")
      (node (ref "U1") (pin "D16") (pinfunction "IO_L16N_1_D16") (pintype "passive"))
    )
    (net (code "103") (name "unconnected-(U1B-IO_L16P_1-PadD14)") (class "Default")
      (node (ref "U1") (pin "D14") (pinfunction "IO_L16P_1_D14") (pintype "passive"))
    )
    (net (code "104") (name "unconnected-(U1B-IO_L17N_1-PadE15)") (class "Default")
      (node (ref "U1") (pin "E15") (pinfunction "IO_L17N_1_E15") (pintype "passive"))
    )
    (net (code "105") (name "unconnected-(U1B-IO_L17P_1-PadF15)") (class "Default")
      (node (ref "U1") (pin "F15") (pinfunction "IO_L17P_1_F15") (pintype "passive"))
    )
    (net (code "106") (name "unconnected-(U1B-IO_L18N_1-PadH16)") (class "Default")
      (node (ref "U1") (pin "H16") (pinfunction "IO_L18N_1_H16") (pintype "passive"))
    )
    (net (code "107") (name "unconnected-(U1B-IO_L18P_1-PadG16)") (class "Default")
      (node (ref "U1") (pin "G16") (pinfunction "IO_L18P_1_G16") (pintype "passive"))
    )
    (net (code "108") (name "unconnected-(U1B-IO_L_1-PadH14)") (class "Default")
      (node (ref "U1") (pin "H14") (pinfunction "IO_L_1_H14") (pintype "passive"))
    )
    (net (code "109") (name "unconnected-(U1B-IO_L_1-PadJ14)") (class "Default")
      (node (ref "U1") (pin "J14") (pinfunction "IO_L_1_J14") (pintype "passive"))
    )
    (net (code "110") (name "unconnected-(U1B-IO_L_GCLKIOL_4_1-PadK14)") (class "Default")
      (node (ref "U1") (pin "K14") (pinfunction "IO_L_GCLKIOL_4_1_K14") (pintype "passive"))
    )
    (net (code "111") (name "unconnected-(U1C-IO_TE1N_2-PadT4)") (class "Default")
      (node (ref "U1") (pin "T4") (pinfunction "IO_TE1N_2_T4") (pintype "passive"))
    )
    (net (code "112") (name "unconnected-(U1C-IO_TE1P_2-PadP6)") (class "Default")
      (node (ref "U1") (pin "P6") (pinfunction "IO_TE1P_2_P6") (pintype "passive"))
    )
    (net (code "113") (name "unconnected-(U1C-IO_TE2N_2-PadT6)") (class "Default")
      (node (ref "U1") (pin "T6") (pinfunction "IO_TE2N_2_T6") (pintype "passive"))
    )
    (net (code "114") (name "unconnected-(U1C-IO_TE2P_2-PadT5)") (class "Default")
      (node (ref "U1") (pin "T5") (pinfunction "IO_TE2P_2_T5") (pintype "passive"))
    )
    (net (code "115") (name "unconnected-(U1C-IO_TE3N_2,D4-PadP5)") (class "Default")
      (node (ref "U1") (pin "P5") (pinfunction "IO_TE3N_2,D4_P5") (pintype "passive"))
    )
    (net (code "116") (name "unconnected-(U1C-IO_TE3P_2,D3-PadN5)") (class "Default")
      (node (ref "U1") (pin "N5") (pinfunction "IO_TE3P_2,D3_N5") (pintype "passive"))
    )
    (net (code "117") (name "unconnected-(U1C-IO_TE4N_2-PadN6)") (class "Default")
      (node (ref "U1") (pin "N6") (pinfunction "IO_TE4N_2_N6") (pintype "passive"))
    )
    (net (code "118") (name "unconnected-(U1C-IO_TE4P_2-PadM6)") (class "Default")
      (node (ref "U1") (pin "M6") (pinfunction "IO_TE4P_2_M6") (pintype "passive"))
    )
    (net (code "119") (name "unconnected-(U1C-IO_TE5N_2-PadM7)") (class "Default")
      (node (ref "U1") (pin "M7") (pinfunction "IO_TE5N_2_M7") (pintype "passive"))
    )
    (net (code "120") (name "unconnected-(U1C-IO_TE5P_2-PadT12)") (class "Default")
      (node (ref "U1") (pin "T12") (pinfunction "IO_TE5P_2_T12") (pintype "passive"))
    )
    (net (code "121") (name "unconnected-(U1C-IO_TE6N_2-PadP8)") (class "Default")
      (node (ref "U1") (pin "P8") (pinfunction "IO_TE6N_2_P8") (pintype "passive"))
    )
    (net (code "122") (name "unconnected-(U1C-IO_TE6P_2,D7-PadR5)") (class "Default")
      (node (ref "U1") (pin "R5") (pinfunction "IO_TE6P_2,D7_R5") (pintype "passive"))
    )
    (net (code "123") (name "unconnected-(U1C-IO_TE7N_2-PadN8)") (class "Default")
      (node (ref "U1") (pin "N8") (pinfunction "IO_TE7N_2_N8") (pintype "passive"))
    )
    (net (code "124") (name "unconnected-(U1C-IO_TE7P_2-PadT9)") (class "Default")
      (node (ref "U1") (pin "T9") (pinfunction "IO_TE7P_2_T9") (pintype "passive"))
    )
    (net (code "125") (name "unconnected-(U1C-IO_TE8N_2-PadP9)") (class "Default")
      (node (ref "U1") (pin "P9") (pinfunction "IO_TE8N_2_P9") (pintype "passive"))
    )
    (net (code "126") (name "unconnected-(U1C-IO_TE8P_2-PadR9)") (class "Default")
      (node (ref "U1") (pin "R9") (pinfunction "IO_TE8P_2_R9") (pintype "passive"))
    )
    (net (code "127") (name "unconnected-(U1C-IO_TE9N_2,D6-PadL7)") (class "Default")
      (node (ref "U1") (pin "L7") (pinfunction "IO_TE9N_2,D6_L7") (pintype "passive"))
    )
    (net (code "128") (name "unconnected-(U1C-IO_TE9P_2,D5-PadL8)") (class "Default")
      (node (ref "U1") (pin "L8") (pinfunction "IO_TE9P_2,D5_L8") (pintype "passive"))
    )
    (net (code "129") (name "unconnected-(U1C-IO_TE10N_GCLKIOT_6_2-PadM9)") (class "Default")
      (node (ref "U1") (pin "M9") (pinfunction "IO_TE10N_GCLKIOT_6_2_M9") (pintype "passive"))
    )
    (net (code "130") (name "unconnected-(U1C-IO_TE10P_GCLKIOT_7_2-PadP7)") (class "Default")
      (node (ref "U1") (pin "P7") (pinfunction "IO_TE10P_GCLKIOT_7_2_P7") (pintype "passive"))
    )
    (net (code "131") (name "unconnected-(U1C-IO_TE11N_GCLKIOT_4_2-PadT7)") (class "Default")
      (node (ref "U1") (pin "T7") (pinfunction "IO_TE11N_GCLKIOT_4_2_T7") (pintype "passive"))
    )
    (net (code "132") (name "unconnected-(U1C-IO_TE12N_GCLKIOT_0_2-PadT8)") (class "Default")
      (node (ref "U1") (pin "T8") (pinfunction "IO_TE12N_GCLKIOT_0_2_T8") (pintype "passive"))
    )
    (net (code "133") (name "unconnected-(U1C-IO_TE12P_GCLKIOT_1_2-PadN9)") (class "Default")
      (node (ref "U1") (pin "N9") (pinfunction "IO_TE12P_GCLKIOT_1_2_N9") (pintype "passive"))
    )
    (net (code "134") (name "unconnected-(U1C-IO_TE13N_GCLKIOT_2_2-PadT13)") (class "Default")
      (node (ref "U1") (pin "T13") (pinfunction "IO_TE13N_GCLKIOT_2_2_T13") (pintype "passive"))
    )
    (net (code "135") (name "unconnected-(U1C-IO_TE13P_GCLKIOT_3_2-PadT14)") (class "Default")
      (node (ref "U1") (pin "T14") (pinfunction "IO_TE13P_GCLKIOT_3_2_T14") (pintype "passive"))
    )
    (net (code "136") (name "unconnected-(U1C-IO_TE15N_2-PadT15)") (class "Default")
      (node (ref "U1") (pin "T15") (pinfunction "IO_TE15N_2_T15") (pintype "passive"))
    )
    (net (code "137") (name "unconnected-(U1C-IO_TE15P_2-PadR15)") (class "Default")
      (node (ref "U1") (pin "R15") (pinfunction "IO_TE15P_2_R15") (pintype "passive"))
    )
    (net (code "138") (name "unconnected-(U1C-IO_TE16N_2-PadR12)") (class "Default")
      (node (ref "U1") (pin "R12") (pinfunction "IO_TE16N_2_R12") (pintype "passive"))
    )
    (net (code "139") (name "unconnected-(U1C-IO_TE16P_2-PadR14)") (class "Default")
      (node (ref "U1") (pin "R14") (pinfunction "IO_TE16P_2_R14") (pintype "passive"))
    )
    (net (code "140") (name "unconnected-(U1C-IO_TE17N_2,ADC_CH_3-PadP11)") (class "Default")
      (node (ref "U1") (pin "P11") (pinfunction "IO_TE17N_2,ADC_CH_3_P11") (pintype "passive"))
    )
    (net (code "141") (name "unconnected-(U1C-IO_TE17P_2,ADC_CH_1-PadM10)") (class "Default")
      (node (ref "U1") (pin "M10") (pinfunction "IO_TE17P_2,ADC_CH_1_M10") (pintype "passive"))
    )
    (net (code "142") (name "unconnected-(U1C-IO_TE18N_2,D2,ADC_CH_6-PadP12)") (class "Default")
      (node (ref "U1") (pin "P12") (pinfunction "IO_TE18N_2,D2,ADC_CH_6_P12") (pintype "passive"))
    )
    (net (code "143") (name "unconnected-(U1C-IO_TE18P_2,D1,ADC_CH_5-PadN12)") (class "Default")
      (node (ref "U1") (pin "N12") (pinfunction "IO_TE18P_2,D1,ADC_CH_5_N12") (pintype "passive"))
    )
    (net (code "144") (name "unconnected-(U1C-IO_TE19N_2,ADC_CH_7-PadR16)") (class "Default")
      (node (ref "U1") (pin "R16") (pinfunction "IO_TE19N_2,ADC_CH_7_R16") (pintype "passive"))
    )
    (net (code "145") (name "unconnected-(U1C-IO_TE19P_2,ADC_CH_4-PadM12)") (class "Default")
      (node (ref "U1") (pin "M12") (pinfunction "IO_TE19P_2,ADC_CH_4_M12") (pintype "passive"))
    )
    (net (code "146") (name "unconnected-(U1C-IO_T_2,ADC_CH_2-PadL10)") (class "Default")
      (node (ref "U1") (pin "L10") (pinfunction "IO_T_2,ADC_CH_2_L10") (pintype "passive"))
    )
    (net (code "147") (name "unconnected-(U1D-IO_R1N_3-PadD3)") (class "Default")
      (node (ref "U1") (pin "D3") (pinfunction "IO_R1N_3_D3") (pintype "passive"))
    )
    (net (code "148") (name "unconnected-(U1D-IO_R1P_3-PadB3)") (class "Default")
      (node (ref "U1") (pin "B3") (pinfunction "IO_R1P_3_B3") (pintype "passive"))
    )
    (net (code "149") (name "unconnected-(U1D-IO_R2N_3-PadE4)") (class "Default")
      (node (ref "U1") (pin "E4") (pinfunction "IO_R2N_3_E4") (pintype "passive"))
    )
    (net (code "150") (name "unconnected-(U1D-IO_R2P_3-PadE3)") (class "Default")
      (node (ref "U1") (pin "E3") (pinfunction "IO_R2P_3_E3") (pintype "passive"))
    )
    (net (code "151") (name "unconnected-(U1D-IO_R3N_3-PadF4)") (class "Default")
      (node (ref "U1") (pin "F4") (pinfunction "IO_R3N_3_F4") (pintype "passive"))
    )
    (net (code "152") (name "unconnected-(U1D-IO_R3P_3-PadF5)") (class "Default")
      (node (ref "U1") (pin "F5") (pinfunction "IO_R3P_3_F5") (pintype "passive"))
    )
    (net (code "153") (name "unconnected-(U1D-IO_R4N_3-PadA2)") (class "Default")
      (node (ref "U1") (pin "A2") (pinfunction "IO_R4N_3_A2") (pintype "passive"))
    )
    (net (code "154") (name "unconnected-(U1D-IO_R4P_3-PadB2)") (class "Default")
      (node (ref "U1") (pin "B2") (pinfunction "IO_R4P_3_B2") (pintype "passive"))
    )
    (net (code "155") (name "unconnected-(U1D-IO_R5N_3-PadC2)") (class "Default")
      (node (ref "U1") (pin "C2") (pinfunction "IO_R5N_3_C2") (pintype "passive"))
    )
    (net (code "156") (name "unconnected-(U1D-IO_R5P_3-PadC3)") (class "Default")
      (node (ref "U1") (pin "C3") (pinfunction "IO_R5P_3_C3") (pintype "passive"))
    )
    (net (code "157") (name "unconnected-(U1D-IO_R6N_3-PadE2)") (class "Default")
      (node (ref "U1") (pin "E2") (pinfunction "IO_R6N_3_E2") (pintype "passive"))
    )
    (net (code "158") (name "unconnected-(U1D-IO_R6P_3-PadC1)") (class "Default")
      (node (ref "U1") (pin "C1") (pinfunction "IO_R6P_3_C1") (pintype "passive"))
    )
    (net (code "159") (name "unconnected-(U1D-IO_R7N_3-PadD1)") (class "Default")
      (node (ref "U1") (pin "D1") (pinfunction "IO_R7N_3_D1") (pintype "passive"))
    )
    (net (code "160") (name "unconnected-(U1D-IO_R7P_3-PadE1)") (class "Default")
      (node (ref "U1") (pin "E1") (pinfunction "IO_R7P_3_E1") (pintype "passive"))
    )
    (net (code "161") (name "unconnected-(U1D-IO_R8N_3-PadF2)") (class "Default")
      (node (ref "U1") (pin "F2") (pinfunction "IO_R8N_3_F2") (pintype "passive"))
    )
    (net (code "162") (name "unconnected-(U1D-IO_R8P_3-PadF1)") (class "Default")
      (node (ref "U1") (pin "F1") (pinfunction "IO_R8P_3_F1") (pintype "passive"))
    )
    (net (code "163") (name "unconnected-(U1D-IO_R9N_3-PadG6)") (class "Default")
      (node (ref "U1") (pin "G6") (pinfunction "IO_R9N_3_G6") (pintype "passive"))
    )
    (net (code "164") (name "unconnected-(U1D-IO_R9P_3-PadG5)") (class "Default")
      (node (ref "U1") (pin "G5") (pinfunction "IO_R9P_3_G5") (pintype "passive"))
    )
    (net (code "165") (name "unconnected-(U1D-IO_R10N_3-PadG3)") (class "Default")
      (node (ref "U1") (pin "G3") (pinfunction "IO_R10N_3_G3") (pintype "passive"))
    )
    (net (code "166") (name "unconnected-(U1D-IO_R10P_3-PadG1)") (class "Default")
      (node (ref "U1") (pin "G1") (pinfunction "IO_R10P_3_G1") (pintype "passive"))
    )
    (net (code "167") (name "unconnected-(U1D-IO_R11N_3-PadH5)") (class "Default")
      (node (ref "U1") (pin "H5") (pinfunction "IO_R11N_3_H5") (pintype "passive"))
    )
    (net (code "168") (name "unconnected-(U1D-IO_R11P_3-PadH1)") (class "Default")
      (node (ref "U1") (pin "H1") (pinfunction "IO_R11P_3_H1") (pintype "passive"))
    )
    (net (code "169") (name "unconnected-(U1D-IO_R12N_3-PadJ1)") (class "Default")
      (node (ref "U1") (pin "J1") (pinfunction "IO_R12N_3_J1") (pintype "passive"))
    )
    (net (code "170") (name "unconnected-(U1D-IO_R12P_3-PadK1)") (class "Default")
      (node (ref "U1") (pin "K1") (pinfunction "IO_R12P_3_K1") (pintype "passive"))
    )
    (net (code "171") (name "unconnected-(U1D-IO_R13N_GCLKIOR_6_3-PadL1)") (class "Default")
      (node (ref "U1") (pin "L1") (pinfunction "IO_R13N_GCLKIOR_6_3_L1") (pintype "passive"))
    )
    (net (code "172") (name "unconnected-(U1D-IO_R13P_GCLKIOR_7_3-PadH2)") (class "Default")
      (node (ref "U1") (pin "H2") (pinfunction "IO_R13P_GCLKIOR_7_3_H2") (pintype "passive"))
    )
    (net (code "173") (name "unconnected-(U1D-IO_R14N_GCLKIOR_0_3-PadH3)") (class "Default")
      (node (ref "U1") (pin "H3") (pinfunction "IO_R14N_GCLKIOR_0_3_H3") (pintype "passive"))
    )
    (net (code "174") (name "unconnected-(U1D-IO_R14P_GCLKIOR_1_3-PadH4)") (class "Default")
      (node (ref "U1") (pin "H4") (pinfunction "IO_R14P_GCLKIOR_1_3_H4") (pintype "passive"))
    )
    (net (code "175") (name "unconnected-(U1D-IO_R15N_GCLKIOR_4_3-PadJ4)") (class "Default")
      (node (ref "U1") (pin "J4") (pinfunction "IO_R15N_GCLKIOR_4_3_J4") (pintype "passive"))
    )
    (net (code "176") (name "unconnected-(U1D-IO_R15P_GCLKIOR_5_3-PadJ3)") (class "Default")
      (node (ref "U1") (pin "J3") (pinfunction "IO_R15P_GCLKIOR_5_3_J3") (pintype "passive"))
    )
    (net (code "177") (name "unconnected-(U1D-IO_R16N_3-PadK2)") (class "Default")
      (node (ref "U1") (pin "K2") (pinfunction "IO_R16N_3_K2") (pintype "passive"))
    )
    (net (code "178") (name "unconnected-(U1D-IO_R16P_3-PadK3)") (class "Default")
      (node (ref "U1") (pin "K3") (pinfunction "IO_R16P_3_K3") (pintype "passive"))
    )
    (net (code "179") (name "unconnected-(U1D-IO_R17N_3-PadJ6)") (class "Default")
      (node (ref "U1") (pin "J6") (pinfunction "IO_R17N_3_J6") (pintype "passive"))
    )
    (net (code "180") (name "unconnected-(U1D-IO_R17P_3-PadK5)") (class "Default")
      (node (ref "U1") (pin "K5") (pinfunction "IO_R17P_3_K5") (pintype "passive"))
    )
    (net (code "181") (name "unconnected-(U1D-IO_R18N_3-PadR1)") (class "Default")
      (node (ref "U1") (pin "R1") (pinfunction "IO_R18N_3_R1") (pintype "passive"))
    )
    (net (code "182") (name "unconnected-(U1D-IO_R18P_3-PadP1)") (class "Default")
      (node (ref "U1") (pin "P1") (pinfunction "IO_R18P_3_P1") (pintype "passive"))
    )
    (net (code "183") (name "unconnected-(U1D-IO_R19N_3-PadP2)") (class "Default")
      (node (ref "U1") (pin "P2") (pinfunction "IO_R19N_3_P2") (pintype "passive"))
    )
    (net (code "184") (name "unconnected-(U1D-IO_R19P_3-PadR2)") (class "Default")
      (node (ref "U1") (pin "R2") (pinfunction "IO_R19P_3_R2") (pintype "passive"))
    )
    (net (code "185") (name "unconnected-(U1D-IO_R20N_3-PadM2)") (class "Default")
      (node (ref "U1") (pin "M2") (pinfunction "IO_R20N_3_M2") (pintype "passive"))
    )
    (net (code "186") (name "unconnected-(U1D-IO_R20P_3-PadL3)") (class "Default")
      (node (ref "U1") (pin "L3") (pinfunction "IO_R20P_3_L3") (pintype "passive"))
    )
    (net (code "187") (name "unconnected-(U1D-IO_R21N_3-PadM3)") (class "Default")
      (node (ref "U1") (pin "M3") (pinfunction "IO_R21N_3_M3") (pintype "passive"))
    )
    (net (code "188") (name "unconnected-(U1D-IO_R21P_3-PadK6)") (class "Default")
      (node (ref "U1") (pin "K6") (pinfunction "IO_R21P_3_K6") (pintype "passive"))
    )
    (net (code "189") (name "unconnected-(U1D-IO_R22N_3-PadN3)") (class "Default")
      (node (ref "U1") (pin "N3") (pinfunction "IO_R22N_3_N3") (pintype "passive"))
    )
    (net (code "190") (name "unconnected-(U1D-IO_R22P_3-PadM4)") (class "Default")
      (node (ref "U1") (pin "M4") (pinfunction "IO_R22P_3_M4") (pintype "passive"))
    )
    (net (code "191") (name "unconnected-(U1D-IO_R23N_3-PadN4)") (class "Default")
      (node (ref "U1") (pin "N4") (pinfunction "IO_R23N_3_N4") (pintype "passive"))
    )
    (net (code "192") (name "unconnected-(U1D-IO_R23P_3-PadP4)") (class "Default")
      (node (ref "U1") (pin "P4") (pinfunction "IO_R23P_3_P4") (pintype "passive"))
    )
    (net (code "193") (name "unconnected-(U1D-IO_R24N_3-PadM1)") (class "Default")
      (node (ref "U1") (pin "M1") (pinfunction "IO_R24N_3_M1") (pintype "passive"))
    )
    (net (code "194") (name "unconnected-(U1D-IO_R24P_3-PadN1)") (class "Default")
      (node (ref "U1") (pin "N1") (pinfunction "IO_R24P_3_N1") (pintype "passive"))
    )
    (net (code "195") (name "unconnected-(U1D-IO_R_3-PadB1)") (class "Default")
      (node (ref "U1") (pin "B1") (pinfunction "IO_R_3_B1") (pintype "passive"))
    )
    (net (code "196") (name "unconnected-(U1D-IO_R_3-PadF3)") (class "Default")
      (node (ref "U1") (pin "F3") (pinfunction "IO_R_3_F3") (pintype "passive"))
    )
    (net (code "197") (name "unconnected-(U1D-IO_R_3-PadL4)") (class "Default")
      (node (ref "U1") (pin "L4") (pinfunction "IO_R_3_L4") (pintype "passive"))
    )
    (net (code "198") (name "unconnected-(U1D-IO_R_3-PadL5)") (class "Default")
      (node (ref "U1") (pin "L5") (pinfunction "IO_R_3_L5") (pintype "passive"))
    )
    (net (code "199") (name "unconnected-(U1D-IO_R_3-PadM5)") (class "Default")
      (node (ref "U1") (pin "M5") (pinfunction "IO_R_3_M5") (pintype "passive"))
    )
    (net (code "200") (name "unconnected-(U1E-ADC_VREF-PadL11)") (class "Default")
      (node (ref "U1") (pin "L11") (pinfunction "ADC_VREF_L11") (pintype "passive"))
    )
    (net (code "201") (name "unconnected-(U1E-IO_B_0,TDI-PadC12)") (class "Default")
      (node (ref "U1") (pin "C12") (pinfunction "IO_B_0,TDI_C12") (pintype "passive+no_connect"))
    )
    (net (code "202") (name "unconnected-(U1E-IO_L3P_1,DONE-PadP13)") (class "Default")
      (node (ref "U1") (pin "P13") (pinfunction "IO_L3P_1,DONE_P13") (pintype "passive"))
    )
    (net (code "203") (name "unconnected-(U1E-IO_L_1,TDO-PadE14)") (class "Default")
      (node (ref "U1") (pin "E14") (pinfunction "IO_L_1,TDO_E14") (pintype "passive+no_connect"))
    )
    (net (code "204") (name "unconnected-(U1E-IO_T_2,ADC_CH_0,M1-PadN11)") (class "Default")
      (node (ref "U1") (pin "N11") (pinfunction "IO_T_2,ADC_CH_0,M1_N11") (pintype "passive"))
    )
    (net (code "205") (name "unconnected-(U1E-IO_T_2,INIT_B-PadR3)") (class "Default")
      (node (ref "U1") (pin "R3") (pinfunction "IO_T_2,INIT_B_R3") (pintype "passive"))
    )
    (net (code "206") (name "unconnected-(U1E-IO_T_2,M0-PadT11)") (class "Default")
      (node (ref "U1") (pin "T11") (pinfunction "IO_T_2,M0_T11") (pintype "passive"))
    )
    (net (code "207") (name "unconnected-(U1E-IO_T_2,PROGRAM_B-PadT2)") (class "Default")
      (node (ref "U1") (pin "T2") (pinfunction "IO_T_2,PROGRAM_B_T2") (pintype "passive"))
    )
    (net (code "208") (name "unconnected-(U3-CTS#-Pad9)") (class "Default")
      (node (ref "U3") (pin "9") (pinfunction "CTS#_9") (pintype "passive"))
    )
    (net (code "209") (name "unconnected-(U3-DCD#-Pad12)") (class "Default")
      (node (ref "U3") (pin "12") (pinfunction "DCD#_12") (pintype "passive"))
    )
    (net (code "210") (name "unconnected-(U3-DSR#-Pad10)") (class "Default")
      (node (ref "U3") (pin "10") (pinfunction "DSR#_10") (pintype "passive"))
    )
    (net (code "211") (name "unconnected-(U3-DTR#-Pad13)") (class "Default")
      (node (ref "U3") (pin "13") (pinfunction "DTR#_13") (pintype "passive"))
    )
    (net (code "212") (name "unconnected-(U3-R232-Pad15)") (class "Default")
      (node (ref "U3") (pin "15") (pinfunction "R232_15") (pintype "passive"))
    )
    (net (code "213") (name "unconnected-(U3-RI#-Pad11)") (class "Default")
      (node (ref "U3") (pin "11") (pinfunction "RI#_11") (pintype "passive"))
    )
    (net (code "214") (name "unconnected-(U3-RTS#-Pad14)") (class "Default")
      (node (ref "U3") (pin "14") (pinfunction "RTS#_14") (pintype "passive"))
    )
    (net (code "215") (name "unconnected-(U3-V3-Pad4)") (class "Default")
      (node (ref "U3") (pin "4") (pinfunction "V3_4") (pintype "passive"))
    )
    (net (code "216") (name "unconnected-(U3-XI-Pad7)") (class "Default")
      (node (ref "U3") (pin "7") (pinfunction "XI_7") (pintype "passive"))
    )
    (net (code "217") (name "unconnected-(U3-XO-Pad8)") (class "Default")
      (node (ref "U3") (pin "8") (pinfunction "XO_8") (pintype "passive"))
    )
    (net (code "218") (name "unconnected-(U5-GND-Pad2)") (class "Default")
      (node (ref "U5") (pin "2") (pinfunction "GND_2") (pintype "power_in"))
    )
    (net (code "219") (name "unconnected-(U5-IO1-Pad1)") (class "Default")
      (node (ref "U5") (pin "1") (pinfunction "IO1_1") (pintype "passive"))
    )
    (net (code "220") (name "unconnected-(U5-IO2-Pad3)") (class "Default")
      (node (ref "U5") (pin "3") (pinfunction "IO2_3") (pintype "passive"))
    )
    (net (code "221") (name "unconnected-(U5-IO3-Pad4)") (class "Default")
      (node (ref "U5") (pin "4") (pinfunction "IO3_4") (pintype "passive"))
    )
    (net (code "222") (name "unconnected-(U5-IO4-Pad6)") (class "Default")
      (node (ref "U5") (pin "6") (pinfunction "IO4_6") (pintype "passive"))
    )
    (net (code "223") (name "unconnected-(U5-VCC-Pad5)") (class "Default")
      (node (ref "U5") (pin "5") (pinfunction "VCC_5") (pintype "power_in"))
    )
    (net (code "224") (name "unconnected-(U6-CTS#-Pad9)") (class "Default")
      (node (ref "U6") (pin "9") (pinfunction "CTS#_9") (pintype "passive"))
    )
    (net (code "225") (name "unconnected-(U6-D+-Pad5)") (class "Default")
      (node (ref "U6") (pin "5") (pinfunction "D+_5") (pintype "passive"))
    )
    (net (code "226") (name "unconnected-(U6-D--Pad6)") (class "Default")
      (node (ref "U6") (pin "6") (pinfunction "D-_6") (pintype "passive"))
    )
    (net (code "227") (name "unconnected-(U6-DCD#-Pad12)") (class "Default")
      (node (ref "U6") (pin "12") (pinfunction "DCD#_12") (pintype "passive"))
    )
    (net (code "228") (name "unconnected-(U6-DSR#-Pad10)") (class "Default")
      (node (ref "U6") (pin "10") (pinfunction "DSR#_10") (pintype "passive"))
    )
    (net (code "229") (name "unconnected-(U6-DTR#-Pad13)") (class "Default")
      (node (ref "U6") (pin "13") (pinfunction "DTR#_13") (pintype "passive"))
    )
    (net (code "230") (name "unconnected-(U6-GND-Pad1)") (class "Default")
      (node (ref "U6") (pin "1") (pinfunction "GND_1") (pintype "passive"))
    )
    (net (code "231") (name "unconnected-(U6-R232-Pad15)") (class "Default")
      (node (ref "U6") (pin "15") (pinfunction "R232_15") (pintype "passive"))
    )
    (net (code "232") (name "unconnected-(U6-RI#-Pad11)") (class "Default")
      (node (ref "U6") (pin "11") (pinfunction "RI#_11") (pintype "passive"))
    )
    (net (code "233") (name "unconnected-(U6-RTS#-Pad14)") (class "Default")
      (node (ref "U6") (pin "14") (pinfunction "RTS#_14") (pintype "passive"))
    )
    (net (code "234") (name "unconnected-(U6-RXD-Pad3)") (class "Default")
      (node (ref "U6") (pin "3") (pinfunction "RXD_3") (pintype "passive"))
    )
    (net (code "235") (name "unconnected-(U6-TXD-Pad2)") (class "Default")
      (node (ref "U6") (pin "2") (pinfunction "TXD_2") (pintype "passive"))
    )
    (net (code "236") (name "unconnected-(U6-V3-Pad4)") (class "Default")
      (node (ref "U6") (pin "4") (pinfunction "V3_4") (pintype "passive"))
    )
    (net (code "237") (name "unconnected-(U6-VCC-Pad16)") (class "Default")
      (node (ref "U6") (pin "16") (pinfunction "VCC_16") (pintype "passive"))
    )
    (net (code "238") (name "unconnected-(U6-XI-Pad7)") (class "Default")
      (node (ref "U6") (pin "7") (pinfunction "XI_7") (pintype "passive"))
    )
    (net (code "239") (name "unconnected-(U6-XO-Pad8)") (class "Default")
      (node (ref "U6") (pin "8") (pinfunction "XO_8") (pintype "passive"))
    )
    (net (code "240") (name "unconnected-(U7-BOOT0-Pad1)") (class "Default")
      (node (ref "U7") (pin "1") (pinfunction "BOOT0_1") (pintype "passive"))
    )
    (net (code "241") (name "unconnected-(U7-NRST-Pad4)") (class "Default")
      (node (ref "U7") (pin "4") (pinfunction "NRST_4") (pintype "passive"))
    )
    (net (code "242") (name "unconnected-(U7-PA0-Pad6)") (class "Default")
      (node (ref "U7") (pin "6") (pinfunction "PA0_6") (pintype "passive"))
    )
    (net (code "243") (name "unconnected-(U7-PA1-Pad7)") (class "Default")
      (node (ref "U7") (pin "7") (pinfunction "PA1_7") (pintype "passive"))
    )
    (net (code "244") (name "unconnected-(U7-PA2-Pad8)") (class "Default")
      (node (ref "U7") (pin "8") (pinfunction "PA2_8") (pintype "passive"))
    )
    (net (code "245") (name "unconnected-(U7-PA3-Pad9)") (class "Default")
      (node (ref "U7") (pin "9") (pinfunction "PA3_9") (pintype "passive"))
    )
    (net (code "246") (name "unconnected-(U7-PA4-Pad10)") (class "Default")
      (node (ref "U7") (pin "10") (pinfunction "PA4_10") (pintype "passive"))
    )
    (net (code "247") (name "unconnected-(U7-PA5-Pad11)") (class "Default")
      (node (ref "U7") (pin "11") (pinfunction "PA5_11") (pintype "passive"))
    )
    (net (code "248") (name "unconnected-(U7-PA6-Pad12)") (class "Default")
      (node (ref "U7") (pin "12") (pinfunction "PA6_12") (pintype "passive"))
    )
    (net (code "249") (name "unconnected-(U7-PA7-Pad13)") (class "Default")
      (node (ref "U7") (pin "13") (pinfunction "PA7_13") (pintype "passive"))
    )
    (net (code "250") (name "unconnected-(U7-PA9-Pad17)") (class "Default")
      (node (ref "U7") (pin "17") (pinfunction "PA9_17") (pintype "passive"))
    )
    (net (code "251") (name "unconnected-(U7-PA10-Pad18)") (class "Default")
      (node (ref "U7") (pin "18") (pinfunction "PA10_18") (pintype "passive"))
    )
    (net (code "252") (name "unconnected-(U7-PA11-Pad19)") (class "Default")
      (node (ref "U7") (pin "19") (pinfunction "PA11_19") (pintype "passive"))
    )
    (net (code "253") (name "unconnected-(U7-PA12-Pad20)") (class "Default")
      (node (ref "U7") (pin "20") (pinfunction "PA12_20") (pintype "passive"))
    )
    (net (code "254") (name "unconnected-(U7-PA15-Pad23)") (class "Default")
      (node (ref "U7") (pin "23") (pinfunction "PA15_23") (pintype "passive"))
    )
    (net (code "255") (name "unconnected-(U7-PB0-Pad14)") (class "Default")
      (node (ref "U7") (pin "14") (pinfunction "PB0_14") (pintype "passive"))
    )
    (net (code "256") (name "unconnected-(U7-PB1-Pad15)") (class "Default")
      (node (ref "U7") (pin "15") (pinfunction "PB1_15") (pintype "passive"))
    )
    (net (code "257") (name "unconnected-(U7-PB3-Pad24)") (class "Default")
      (node (ref "U7") (pin "24") (pinfunction "PB3_24") (pintype "passive"))
    )
    (net (code "258") (name "unconnected-(U7-PB4-Pad25)") (class "Default")
      (node (ref "U7") (pin "25") (pinfunction "PB4_25") (pintype "passive"))
    )
    (net (code "259") (name "unconnected-(U7-PB5-Pad26)") (class "Default")
      (node (ref "U7") (pin "26") (pinfunction "PB5_26") (pintype "passive"))
    )
    (net (code "260") (name "unconnected-(U7-PB6-Pad27)") (class "Default")
      (node (ref "U7") (pin "27") (pinfunction "PB6_27") (pintype "passive"))
    )
    (net (code "261") (name "unconnected-(U7-PB7-Pad28)") (class "Default")
      (node (ref "U7") (pin "28") (pinfunction "PB7_28") (pintype "passive"))
    )
    (net (code "262") (name "unconnected-(U8-NC-Pad4)") (class "Default")
      (node (ref "U8") (pin "4") (pinfunction "NC_4") (pintype "passive"))
    )
    (net (code "263") (name "unconnected-(U9-FB-Pad5)") (class "Default")
      (node (ref "U9") (pin "5") (pinfunction "FB_5") (pintype "passive"))
    )
    (net (code "264") (name "unconnected-(U9-LX-Pad3)") (class "Default")
      (node (ref "U9") (pin "3") (pinfunction "LX_3") (pintype "passive"))
    )
    (net (code "265") (name "unconnected-(U10-ANODE-Pad3)") (class "Default")
      (node (ref "U10") (pin "3") (pinfunction "ANODE_3") (pintype "passive"))
    )
    (net (code "266") (name "unconnected-(U10-CATHODE-Pad1)") (class "Default")
      (node (ref "U10") (pin "1") (pinfunction "CATHODE_1") (pintype "passive"))
    )
    (net (code "267") (name "unconnected-(U10-REF-Pad2)") (class "Default")
      (node (ref "U10") (pin "2") (pinfunction "REF_2") (pintype "input+no_connect"))
    )
  )
)
